# evenFieldDriverBoard.net
KiCad netlist of a schematic drawn in EAGLE
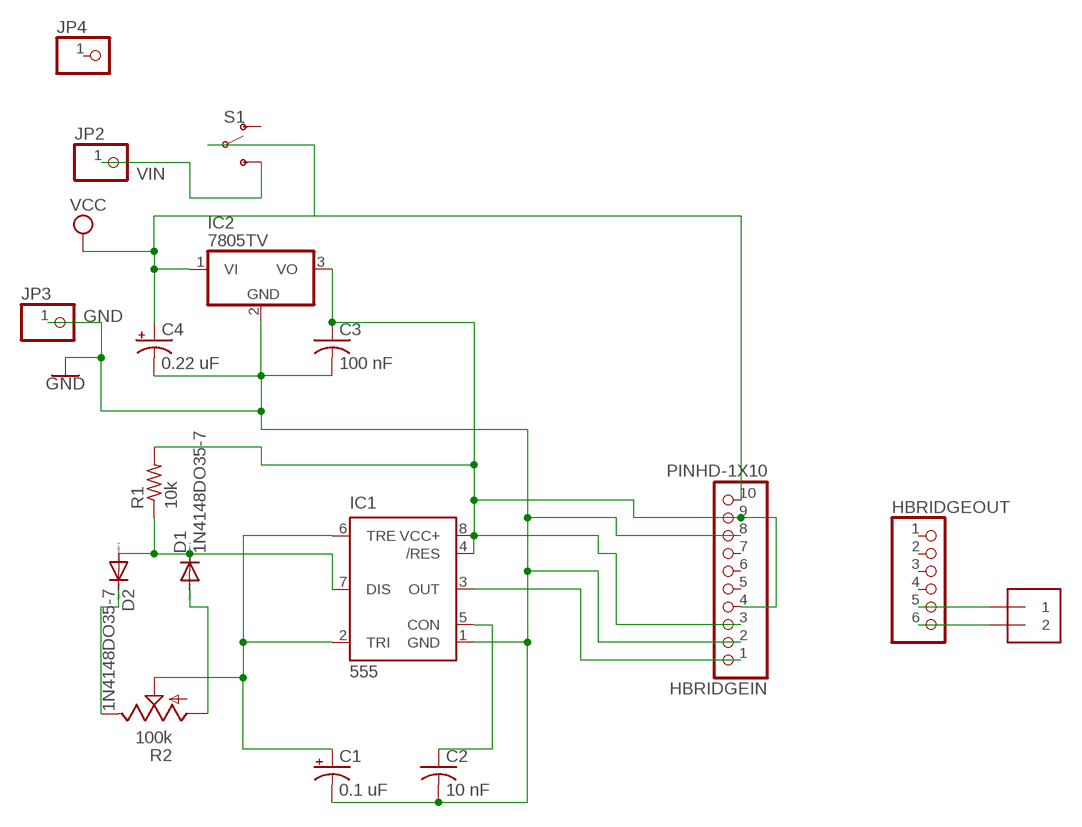
[diagram p0: schematic, sheet 1]

(export (version "E")
  (design (tool "Eeschema 10.0.6"))
  (components
    (comp (ref "C1")
      (value "0.1 uF")
      (footprint "eagle-import:B45181A")
      (libsource (lib "eagle-import") (part "CPOL-USB45181A"))
    )
    (comp (ref "C2")
      (value "10 nF")
      (footprint "eagle-import:C025-025X050")
      (libsource (lib "eagle-import") (part "C-US025-025X050"))
    )
    (comp (ref "C3")
      (value "100 nF")
      (footprint "eagle-import:C025-025X050")
      (libsource (lib "eagle-import") (part "C-US025-025X050"))
    )
    (comp (ref "C4")
      (value "0.22 uF")
      (footprint "eagle-import:B45181A")
      (libsource (lib "eagle-import") (part "CPOL-USB45181A"))
    )
    (comp (ref "D1")
      (value "1N4148DO35-7")
      (footprint "eagle-import:DO35-7")
      (libsource (lib "eagle-import") (part "1N4148DO35-7"))
    )
    (comp (ref "D2")
      (value "1N4148DO35-7")
      (footprint "eagle-import:DO35-7")
      (libsource (lib "eagle-import") (part "1N4148DO35-7"))
    )
    (comp (ref "HBRIDGEIN")
      (value "PINHD-1X10")
      (footprint "eagle-import:1X10-BIG")
      (libsource (lib "eagle-import") (part "PINHD-1X10"))
    )
    (comp (ref "HBRIDGEOUT")
      (value "PINHD-1X6")
      (footprint "eagle-import:1X06")
      (libsource (lib "eagle-import") (part "PINHD-1X6"))
    )
    (comp (ref "IC1")
      (value "555")
      (footprint "eagle-import:DIP08")
      (libsource (lib "eagle-import") (part "555P"))
    )
    (comp (ref "IC2")
      (value "7805TV")
      (footprint "eagle-import:TO220V")
      (libsource (lib "eagle-import") (part "78TV05"))
    )
    (comp (ref "J1")
      (value "1X2-3.5MM")
      (footprint "eagle-import:1X2-3.5MM")
      (libsource (lib "eagle-import") (part "1X2-3.5MM"))
    )
    (comp (ref "JP2")
      (value "PINHD-1X1")
      (footprint "eagle-import:1X01")
      (libsource (lib "eagle-import") (part "PINHD-1X1"))
    )
    (comp (ref "JP3")
      (value "PINHD-1X1")
      (footprint "eagle-import:1X01")
      (libsource (lib "eagle-import") (part "PINHD-1X1"))
    )
    (comp (ref "JP4")
      (value "PINHD-1X1")
      (footprint "eagle-import:1X01")
      (libsource (lib "eagle-import") (part "PINHD-1X1"))
    )
    (comp (ref "R1")
      (value "10k")
      (footprint "eagle-import:0309V")
      (libsource (lib "eagle-import") (part "R-US_0309/V"))
    )
    (comp (ref "R2")
      (value "100k")
      (footprint "eagle-import:RJ9W")
      (libsource (lib "eagle-import") (part "TRIM_US-RJ9W"))
    )
    (comp (ref "S1")
      (value "SWITCH-SPDT-PTH-11.6X4.0MM")
      (footprint "eagle-import:SWITCH_SPDT_PTH_11.6X4.0MM")
      (libsource (lib "eagle-import") (part "SWITCH-SPDT-PTH-11.6X4.0MM"))
    )
  )
  (nets
    (net (code "1") (name "/VIN") (class "Default")
      (node (ref "JP2") (pin "1") (pinfunction "1_1") (pintype "passive"))
      (node (ref "S1") (pin "3") (pinfunction "S_3") (pintype "passive"))
    )
    (net (code "2") (name "GND") (class "Default")
      (node (ref "C1") (pin "-") (pinfunction "-_-") (pintype "passive"))
      (node (ref "C2") (pin "2") (pinfunction "2_2") (pintype "passive"))
      (node (ref "C3") (pin "2") (pinfunction "2_2") (pintype "passive"))
      (node (ref "C4") (pin "-") (pinfunction "-_-") (pintype "passive"))
      (node (ref "HBRIDGEIN") (pin "2") (pinfunction "2_2") (pintype "passive"))
      (node (ref "HBRIDGEIN") (pin "8") (pinfunction "8_8") (pintype "passive"))
      (node (ref "IC1") (pin "1") (pinfunction "GND_1") (pintype "power_in"))
      (node (ref "IC2") (pin "2") (pinfunction "GND_2") (pintype "passive"))
      (node (ref "JP3") (pin "1") (pinfunction "1_1") (pintype "passive"))
    )
    (net (code "3") (name "Net-(D1-PadA)") (class "Default")
      (node (ref "D1") (pin "A") (pinfunction "A_A") (pintype "passive"))
      (node (ref "R2") (pin "A") (pinfunction "A_A") (pintype "passive"))
    )
    (net (code "4") (name "Net-(D2-PadC)") (class "Default")
      (node (ref "D2") (pin "C") (pinfunction "C_C") (pintype "passive"))
      (node (ref "R2") (pin "E") (pinfunction "E_E") (pintype "passive"))
    )
    (net (code "5") (name "Net-(HBRIDGEOUT-Pad5)") (class "Default")
      (node (ref "HBRIDGEOUT") (pin "5") (pinfunction "5_5") (pintype "passive"))
      (node (ref "J1") (pin "1") (pinfunction "1_1") (pintype "passive"))
    )
    (net (code "6") (name "Net-(HBRIDGEOUT-Pad6)") (class "Default")
      (node (ref "HBRIDGEOUT") (pin "6") (pinfunction "6_6") (pintype "passive"))
      (node (ref "J1") (pin "2") (pinfunction "2_2") (pintype "passive"))
    )
    (net (code "7") (name "Net-(IC1-CON)") (class "Default")
      (node (ref "C2") (pin "1") (pinfunction "1_1") (pintype "passive"))
      (node (ref "IC1") (pin "5") (pinfunction "CON_5") (pintype "input"))
    )
    (net (code "8") (name "Net-(IC1-DIS)") (class "Default")
      (node (ref "D1") (pin "C") (pinfunction "C_C") (pintype "passive"))
      (node (ref "D2") (pin "A") (pinfunction "A_A") (pintype "passive"))
      (node (ref "IC1") (pin "7") (pinfunction "DIS_7") (pintype "input"))
      (node (ref "R1") (pin "1") (pinfunction "1_1") (pintype "passive"))
    )
    (net (code "9") (name "Net-(IC1-OUT)") (class "Default")
      (node (ref "HBRIDGEIN") (pin "1") (pinfunction "1_1") (pintype "passive"))
      (node (ref "IC1") (pin "3") (pinfunction "OUT_3") (pintype "output"))
    )
    (net (code "10") (name "Net-(IC1-TRE)") (class "Default")
      (node (ref "C1") (pin "+") (pinfunction "+_+") (pintype "passive"))
      (node (ref "IC1") (pin "2") (pinfunction "TRI_2") (pintype "input"))
      (node (ref "IC1") (pin "6") (pinfunction "TRE_6") (pintype "input"))
      (node (ref "R2") (pin "S") (pinfunction "S_S") (pintype "passive"))
    )
    (net (code "11") (name "Net-(IC1-VCC+)") (class "Default")
      (node (ref "C3") (pin "1") (pinfunction "1_1") (pintype "passive"))
      (node (ref "HBRIDGEIN") (pin "3") (pinfunction "3_3") (pintype "passive"))
      (node (ref "HBRIDGEIN") (pin "4") (pinfunction "4_4") (pintype "passive"))
      (node (ref "HBRIDGEIN") (pin "9") (pinfunction "9_9") (pintype "passive"))
      (node (ref "IC1") (pin "4") (pinfunction "/RES_4") (pintype "input"))
      (node (ref "IC1") (pin "8") (pinfunction "VCC+_8") (pintype "power_in"))
      (node (ref "IC2") (pin "3") (pinfunction "VO_3") (pintype "passive"))
      (node (ref "R1") (pin "2") (pinfunction "2_2") (pintype "passive"))
    )
    (net (code "12") (name "VCC") (class "Default")
      (node (ref "C4") (pin "+") (pinfunction "+_+") (pintype "passive"))
      (node (ref "HBRIDGEIN") (pin "10") (pinfunction "10_10") (pintype "passive"))
      (node (ref "IC2") (pin "1") (pinfunction "VI_1") (pintype "input"))
      (node (ref "S1") (pin "2") (pinfunction "P_2") (pintype "passive"))
    )
    (net (code "13") (name "unconnected-(HBRIDGEIN-Pad5)") (class "Default")
      (node (ref "HBRIDGEIN") (pin "5") (pinfunction "5_5") (pintype "passive"))
    )
    (net (code "14") (name "unconnected-(HBRIDGEIN-Pad6)") (class "Default")
      (node (ref "HBRIDGEIN") (pin "6") (pinfunction "6_6") (pintype "passive"))
    )
    (net (code "15") (name "unconnected-(HBRIDGEIN-Pad7)") (class "Default")
      (node (ref "HBRIDGEIN") (pin "7") (pinfunction "7_7") (pintype "passive"))
    )
    (net (code "16") (name "unconnected-(HBRIDGEOUT-Pad1)") (class "Default")
      (node (ref "HBRIDGEOUT") (pin "1") (pinfunction "1_1") (pintype "passive"))
    )
    (net (code "17") (name "unconnected-(HBRIDGEOUT-Pad2)") (class "Default")
      (node (ref "HBRIDGEOUT") (pin "2") (pinfunction "2_2") (pintype "passive"))
    )
    (net (code "18") (name "unconnected-(HBRIDGEOUT-Pad3)") (class "Default")
      (node (ref "HBRIDGEOUT") (pin "3") (pinfunction "3_3") (pintype "passive"))
    )
    (net (code "19") (name "unconnected-(HBRIDGEOUT-Pad4)") (class "Default")
      (node (ref "HBRIDGEOUT") (pin "4") (pinfunction "4_4") (pintype "passive"))
    )
    (net (code "20") (name "unconnected-(JP4-Pad1)") (class "Default")
      (node (ref "JP4") (pin "1") (pinfunction "1_1") (pintype "passive"))
    )
    (net (code "21") (name "unconnected-(S1-O-Pad1)") (class "Default")
      (node (ref "S1") (pin "1") (pinfunction "O_1") (pintype "passive"))
    )
  )
)
